# InverterSum.net
KiCad netlist of a schematic drawn in Altium Designer
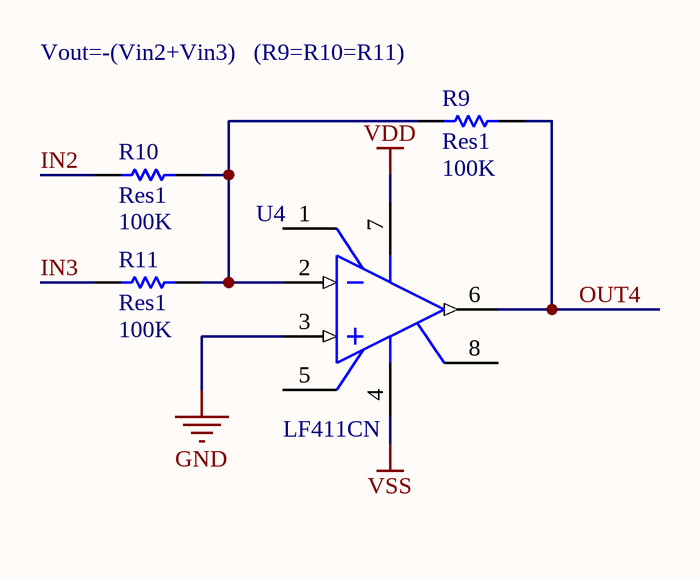
[diagram p0: InverterSum.SchDoc]

(export (version "E")
  (design (tool "Eeschema 10.0.6"))
  (components
    (comp (ref "R9")
      (value "Res1")
      (footprint "AXIAL-0.3")
      (description "Resistor")
      (fields (field (name "ALTIUM_VALUE") "100K") (field (name "PUBLISHER") "Altium Limited"))
      (libsource (lib "Miscellaneous Devices") (part "Res1"))
    )
    (comp (ref "R10")
      (value "Res1")
      (footprint "AXIAL-0.3")
      (description "Resistor")
      (fields (field (name "ALTIUM_VALUE") "100K") (field (name "PUBLISHER") "Altium Limited"))
      (libsource (lib "Miscellaneous Devices") (part "Res1"))
    )
    (comp (ref "R11")
      (value "Res1")
      (footprint "AXIAL-0.3")
      (description "Resistor")
      (fields (field (name "ALTIUM_VALUE") "100K") (field (name "PUBLISHER") "Altium Limited"))
      (libsource (lib "Miscellaneous Devices") (part "Res1"))
    )
    (comp (ref "U4")
      (value "LF411CN")
      (footprint "N08E")
      (description "Low Offset, Low Drift JFET Input Operational Amplifier, 8-pin MDIP")
      (fields
        (field (name "MANUFACTURER") "National Semiconductor")
        (field (name "PUBLISHER") "Altium Limited")
      )
      (libsource (lib "NSC Amplifier") (part "LF411CN"))
    )
  )
  (nets
    (net (code "1") (name "/IN2") (class "Default")
      (node (ref "R10") (pin "2") (pinfunction "2_2") (pintype "passive"))
    )
    (net (code "2") (name "/IN3") (class "Default")
      (node (ref "R11") (pin "2") (pinfunction "2_2") (pintype "passive"))
    )
    (net (code "3") (name "/OUT4") (class "Default")
      (node (ref "R9") (pin "1") (pinfunction "1_1") (pintype "passive"))
      (node (ref "U4") (pin "6") (pinfunction "OUT_6") (pintype "output"))
    )
    (net (code "4") (name "GND") (class "Default")
      (node (ref "U4") (pin "3") (pinfunction "IN+_3") (pintype "input"))
    )
    (net (code "5") (name "Net-(U4-IN-)") (class "Default")
      (node (ref "R10") (pin "1") (pinfunction "1_1") (pintype "passive"))
      (node (ref "R11") (pin "1") (pinfunction "1_1") (pintype "passive"))
      (node (ref "R9") (pin "2") (pinfunction "2_2") (pintype "passive"))
      (node (ref "U4") (pin "2") (pinfunction "IN-_2") (pintype "input"))
    )
    (net (code "6") (name "VDD") (class "Default")
      (node (ref "U4") (pin "7") (pinfunction "V+_7") (pintype "power_in"))
    )
    (net (code "7") (name "VSS") (class "Default")
      (node (ref "U4") (pin "4") (pinfunction "V-_4") (pintype "power_in"))
    )
    (net (code "8") (name "unconnected-(U4-BAL-Pad1)") (class "Default")
      (node (ref "U4") (pin "1") (pinfunction "BAL_1") (pintype "passive"))
    )
    (net (code "9") (name "unconnected-(U4-BAL-Pad5)") (class "Default")
      (node (ref "U4") (pin "5") (pinfunction "BAL_5") (pintype "passive"))
    )
    (net (code "10") (name "unconnected-(U4-NC-Pad8)") (class "Default")
      (node (ref "U4") (pin "8") (pinfunction "NC_8") (pintype "passive"))
    )
  )
)
